# Encoder.net
KiCad netlist of a schematic drawn in EAGLE
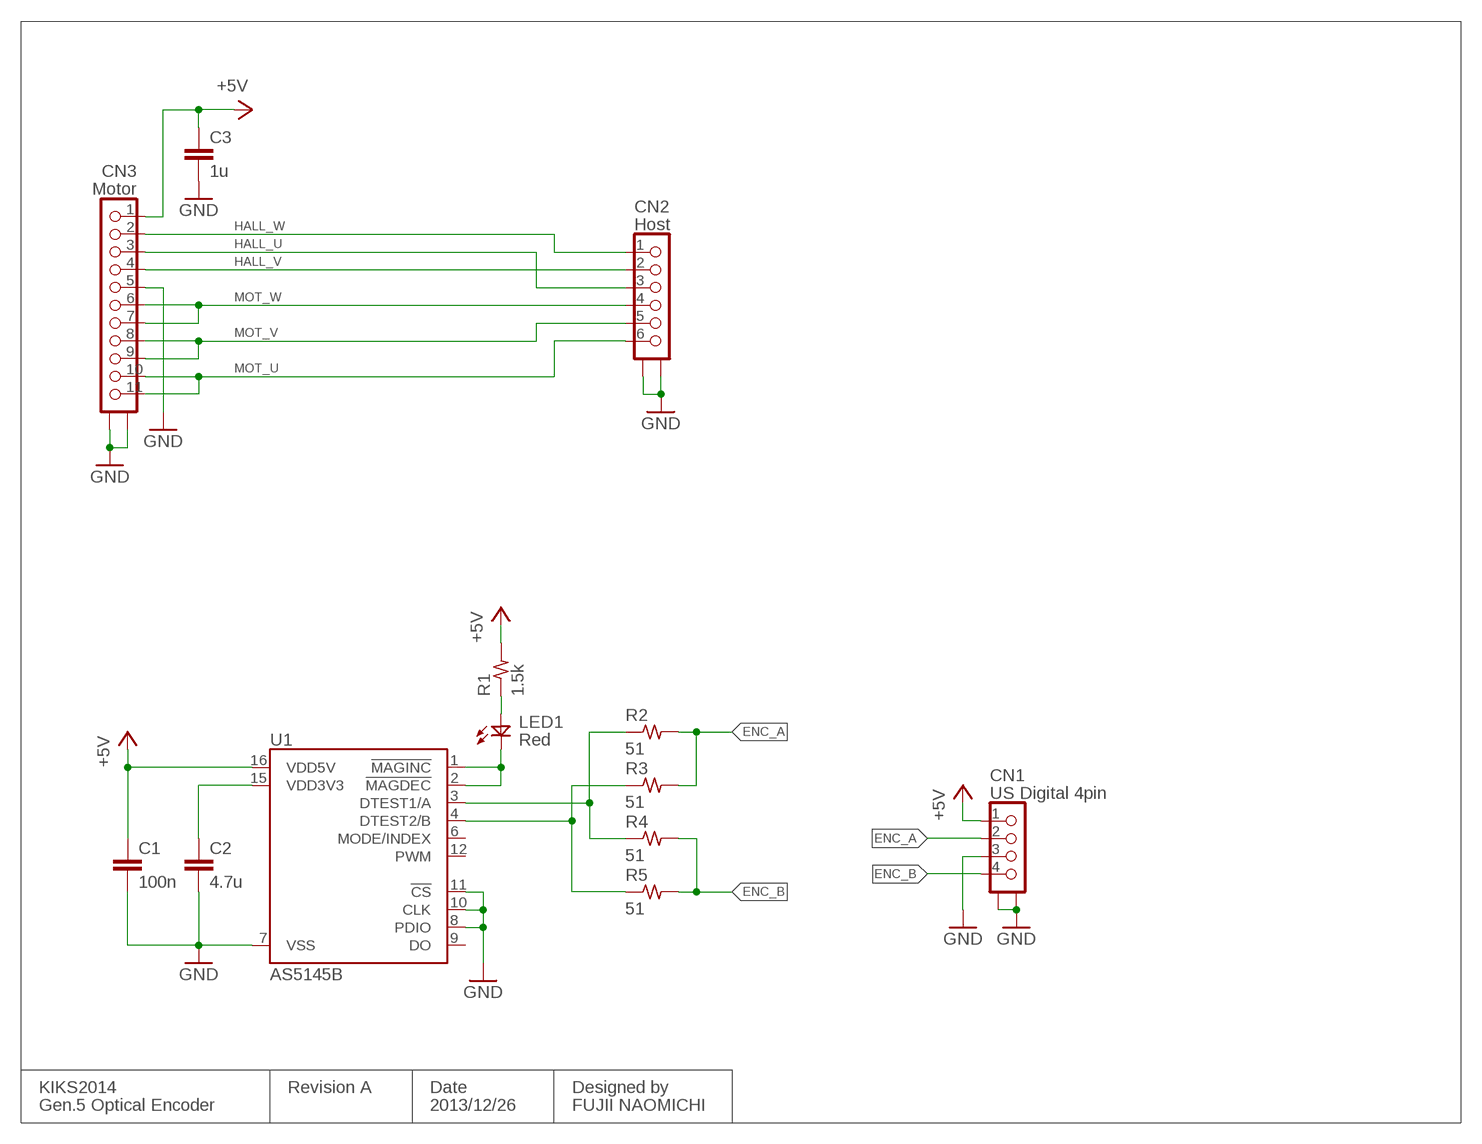
[diagram p0: schematic, sheet 1]

(export (version "E")
  (design (tool "Eeschema 10.0.6"))
  (components
    (comp (ref "C1")
      (value "100n")
      (footprint "eagle-import:1608")
      (libsource (lib "eagle-import") (part "C1608"))
    )
    (comp (ref "C2")
      (value "4.7u")
      (footprint "eagle-import:1608")
      (libsource (lib "eagle-import") (part "C1608"))
    )
    (comp (ref "C3")
      (value "1u")
      (footprint "eagle-import:1608")
      (libsource (lib "eagle-import") (part "C1608"))
    )
    (comp (ref "CN1")
      (value "US Digital 4pin")
      (footprint "eagle-import:53261-04")
      (libsource (lib "eagle-import") (part "53261-0471"))
    )
    (comp (ref "CN2")
      (value "Host")
      (footprint "eagle-import:504050-0691")
      (libsource (lib "eagle-import") (part "504050-0691"))
    )
    (comp (ref "CN3")
      (value "Motor")
      (footprint "eagle-import:52271-11")
      (libsource (lib "eagle-import") (part "52271-1179"))
    )
    (comp (ref "LED1")
      (value "Red")
      (footprint "eagle-import:1608")
      (libsource (lib "eagle-import") (part "LED1608"))
    )
    (comp (ref "R1")
      (value "1.5k")
      (footprint "eagle-import:1608")
      (libsource (lib "eagle-import") (part "R1608"))
    )
    (comp (ref "R2")
      (value "51")
      (footprint "eagle-import:1608")
      (libsource (lib "eagle-import") (part "R1608"))
    )
    (comp (ref "R3")
      (value "51")
      (footprint "eagle-import:1608")
      (libsource (lib "eagle-import") (part "R1608"))
    )
    (comp (ref "R4")
      (value "51")
      (footprint "eagle-import:1608")
      (libsource (lib "eagle-import") (part "R1608"))
    )
    (comp (ref "R5")
      (value "51")
      (footprint "eagle-import:1608")
      (libsource (lib "eagle-import") (part "R1608"))
    )
    (comp (ref "U1")
      (value "AS5145B")
      (footprint "eagle-import:SSOP16")
      (libsource (lib "eagle-import") (part "AS5145B"))
    )
  )
  (nets
    (net (code "1") (name "+5V") (class "Default")
      (node (ref "C1") (pin "1") (pinfunction "1_1") (pintype "passive"))
      (node (ref "C3") (pin "1") (pinfunction "1_1") (pintype "passive"))
      (node (ref "CN1") (pin "1") (pinfunction "1_1") (pintype "passive"))
      (node (ref "CN3") (pin "1") (pinfunction "1_1") (pintype "passive"))
      (node (ref "R1") (pin "2") (pinfunction "2_2") (pintype "passive"))
      (node (ref "U1") (pin "16") (pinfunction "VDD5V_16") (pintype "bidirectional"))
    )
    (net (code "2") (name "/HALL_U") (class "Default")
      (node (ref "CN2") (pin "3") (pinfunction "3_3") (pintype "passive"))
      (node (ref "CN3") (pin "3") (pinfunction "3_3") (pintype "passive"))
    )
    (net (code "3") (name "/HALL_V") (class "Default")
      (node (ref "CN2") (pin "2") (pinfunction "2_2") (pintype "passive"))
      (node (ref "CN3") (pin "4") (pinfunction "4_4") (pintype "passive"))
    )
    (net (code "4") (name "/HALL_W") (class "Default")
      (node (ref "CN2") (pin "1") (pinfunction "1_1") (pintype "passive"))
      (node (ref "CN3") (pin "2") (pinfunction "2_2") (pintype "passive"))
    )
    (net (code "5") (name "/MOT_U") (class "Default")
      (node (ref "CN2") (pin "6") (pinfunction "6_6") (pintype "passive"))
      (node (ref "CN3") (pin "10") (pinfunction "10_10") (pintype "passive"))
      (node (ref "CN3") (pin "11") (pinfunction "11_11") (pintype "passive"))
    )
    (net (code "6") (name "/MOT_V") (class "Default")
      (node (ref "CN2") (pin "5") (pinfunction "5_5") (pintype "passive"))
      (node (ref "CN3") (pin "8") (pinfunction "8_8") (pintype "passive"))
      (node (ref "CN3") (pin "9") (pinfunction "9_9") (pintype "passive"))
    )
    (net (code "7") (name "/MOT_W") (class "Default")
      (node (ref "CN2") (pin "4") (pinfunction "4_4") (pintype "passive"))
      (node (ref "CN3") (pin "6") (pinfunction "6_6") (pintype "passive"))
      (node (ref "CN3") (pin "7") (pinfunction "7_7") (pintype "passive"))
    )
    (net (code "8") (name "ENC_A") (class "Default")
      (node (ref "CN1") (pin "2") (pinfunction "2_2") (pintype "passive"))
      (node (ref "R2") (pin "2") (pinfunction "2_2") (pintype "passive"))
      (node (ref "R3") (pin "2") (pinfunction "2_2") (pintype "passive"))
    )
    (net (code "9") (name "ENC_B") (class "Default")
      (node (ref "CN1") (pin "4") (pinfunction "4_4") (pintype "passive"))
      (node (ref "R4") (pin "2") (pinfunction "2_2") (pintype "passive"))
      (node (ref "R5") (pin "2") (pinfunction "2_2") (pintype "passive"))
    )
    (net (code "10") (name "GND") (class "Default")
      (node (ref "C1") (pin "2") (pinfunction "2_2") (pintype "passive"))
      (node (ref "C2") (pin "2") (pinfunction "2_2") (pintype "passive"))
      (node (ref "C3") (pin "2") (pinfunction "2_2") (pintype "passive"))
      (node (ref "CN1") (pin "3") (pinfunction "3_3") (pintype "passive"))
      (node (ref "CN1") (pin "S1") (pinfunction "S1_S1") (pintype "passive"))
      (node (ref "CN1") (pin "S2") (pinfunction "S2_S2") (pintype "passive"))
      (node (ref "CN2") (pin "S1") (pinfunction "S1_S1") (pintype "passive"))
      (node (ref "CN2") (pin "S2") (pinfunction "S2_S2") (pintype "passive"))
      (node (ref "CN3") (pin "5") (pinfunction "5_5") (pintype "passive"))
      (node (ref "CN3") (pin "S1") (pinfunction "S1_S1") (pintype "passive"))
      (node (ref "CN3") (pin "S2") (pinfunction "S2_S2") (pintype "passive"))
      (node (ref "U1") (pin "10") (pinfunction "CLK_10") (pintype "bidirectional"))
      (node (ref "U1") (pin "11") (pinfunction "~{CS}_11") (pintype "bidirectional"))
      (node (ref "U1") (pin "7") (pinfunction "VSS_7") (pintype "bidirectional"))
      (node (ref "U1") (pin "8") (pinfunction "PDIO_8") (pintype "bidirectional"))
    )
    (net (code "11") (name "Net-(LED1-PadA)") (class "Default")
      (node (ref "LED1") (pin "A") (pinfunction "A_A") (pintype "passive"))
      (node (ref "R1") (pin "1") (pinfunction "1_1") (pintype "passive"))
    )
    (net (code "12") (name "Net-(U1-DTEST1{slash}A)") (class "Default")
      (node (ref "R2") (pin "1") (pinfunction "1_1") (pintype "passive"))
      (node (ref "R4") (pin "1") (pinfunction "1_1") (pintype "passive"))
      (node (ref "U1") (pin "3") (pinfunction "DTEST1/A_3") (pintype "bidirectional"))
    )
    (net (code "13") (name "Net-(U1-DTEST2{slash}B)") (class "Default")
      (node (ref "R3") (pin "1") (pinfunction "1_1") (pintype "passive"))
      (node (ref "R5") (pin "1") (pinfunction "1_1") (pintype "passive"))
      (node (ref "U1") (pin "4") (pinfunction "DTEST2/B_4") (pintype "bidirectional"))
    )
    (net (code "14") (name "Net-(U1-VDD3V3)") (class "Default")
      (node (ref "C2") (pin "1") (pinfunction "1_1") (pintype "passive"))
      (node (ref "U1") (pin "15") (pinfunction "VDD3V3_15") (pintype "bidirectional"))
    )
    (net (code "15") (name "Net-(U1-~{MAGDEC})") (class "Default")
      (node (ref "LED1") (pin "K") (pinfunction "K_K") (pintype "passive"))
      (node (ref "U1") (pin "1") (pinfunction "~{MAGINC}_1") (pintype "bidirectional"))
      (node (ref "U1") (pin "2") (pinfunction "~{MAGDEC}_2") (pintype "bidirectional"))
    )
    (net (code "16") (name "unconnected-(U1-DO-Pad9)") (class "Default")
      (node (ref "U1") (pin "9") (pinfunction "DO_9") (pintype "bidirectional"))
    )
    (net (code "17") (name "unconnected-(U1-MODE{slash}INDEX-Pad6)") (class "Default")
      (node (ref "U1") (pin "6") (pinfunction "MODE/INDEX_6") (pintype "bidirectional"))
    )
    (net (code "18") (name "unconnected-(U1-PWM-Pad12)") (class "Default")
      (node (ref "U1") (pin "12") (pinfunction "PWM_12") (pintype "bidirectional"))
    )
  )
)
